# Optoisolator_Pair.net
KiCad netlist of a schematic drawn in Altium Designer
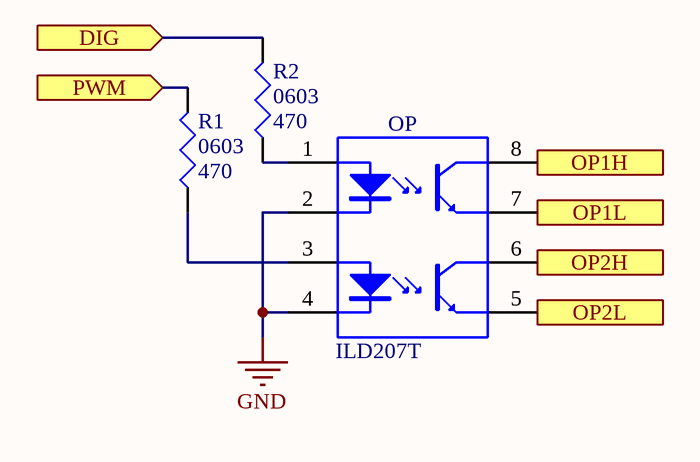
[diagram p0: Optoisolator Pair.SchDoc]

(export (version "E")
  (design (tool "Eeschema 10.0.6"))
  (components
    (comp (ref "OP")
      (value "ILD207T")
      (footprint "VISH-SOIC-8_C_V")
      (fields (field (name "MANUFACTURER") "Vishay"))
      (libsource (lib "Altium Content Vault") (part "OPTO-AKAKECEC-8"))
    )
    (comp (ref "R1")
      (value "0603")
      (footprint "J1-0603")
      (description "Resistor")
      (fields (field (name "ALTIUM_VALUE") "470") (field (name "PUBLISHER") "Altium Limited"))
      (libsource (lib "Miscellaneous Devices") (part "Res3"))
    )
    (comp (ref "R2")
      (value "0603")
      (footprint "J1-0603")
      (description "Resistor")
      (fields (field (name "ALTIUM_VALUE") "470") (field (name "PUBLISHER") "Altium Limited"))
      (libsource (lib "Miscellaneous Devices") (part "Res3"))
    )
  )
  (nets
    (net (code "1") (name "/DIG") (class "Default")
      (node (ref "R2") (pin "2") (pinfunction "2_2") (pintype "passive"))
    )
    (net (code "2") (name "/OP1H") (class "Default")
      (node (ref "OP") (pin "8") (pinfunction "C_8") (pintype "passive"))
    )
    (net (code "3") (name "/OP1L") (class "Default")
      (node (ref "OP") (pin "7") (pinfunction "E_7") (pintype "passive"))
    )
    (net (code "4") (name "/OP2H") (class "Default")
      (node (ref "OP") (pin "6") (pinfunction "C_6") (pintype "passive"))
    )
    (net (code "5") (name "/OP2L") (class "Default")
      (node (ref "OP") (pin "5") (pinfunction "E_5") (pintype "passive"))
    )
    (net (code "6") (name "/PWM") (class "Default")
      (node (ref "R1") (pin "2") (pinfunction "2_2") (pintype "passive"))
    )
    (net (code "7") (name "GND") (class "Default")
      (node (ref "OP") (pin "2") (pinfunction "K_2") (pintype "passive"))
      (node (ref "OP") (pin "4") (pinfunction "K_4") (pintype "passive"))
    )
    (net (code "8") (name "Net-(OP-A-Pad1)") (class "Default")
      (node (ref "OP") (pin "1") (pinfunction "A_1") (pintype "passive"))
      (node (ref "R2") (pin "1") (pinfunction "1_1") (pintype "passive"))
    )
    (net (code "9") (name "Net-(OP-A-Pad3)") (class "Default")
      (node (ref "OP") (pin "3") (pinfunction "A_3") (pintype "passive"))
      (node (ref "R1") (pin "1") (pinfunction "1_1") (pintype "passive"))
    )
  )
)
